# stereo-encoder.net
KiCad netlist of a schematic drawn in EAGLE
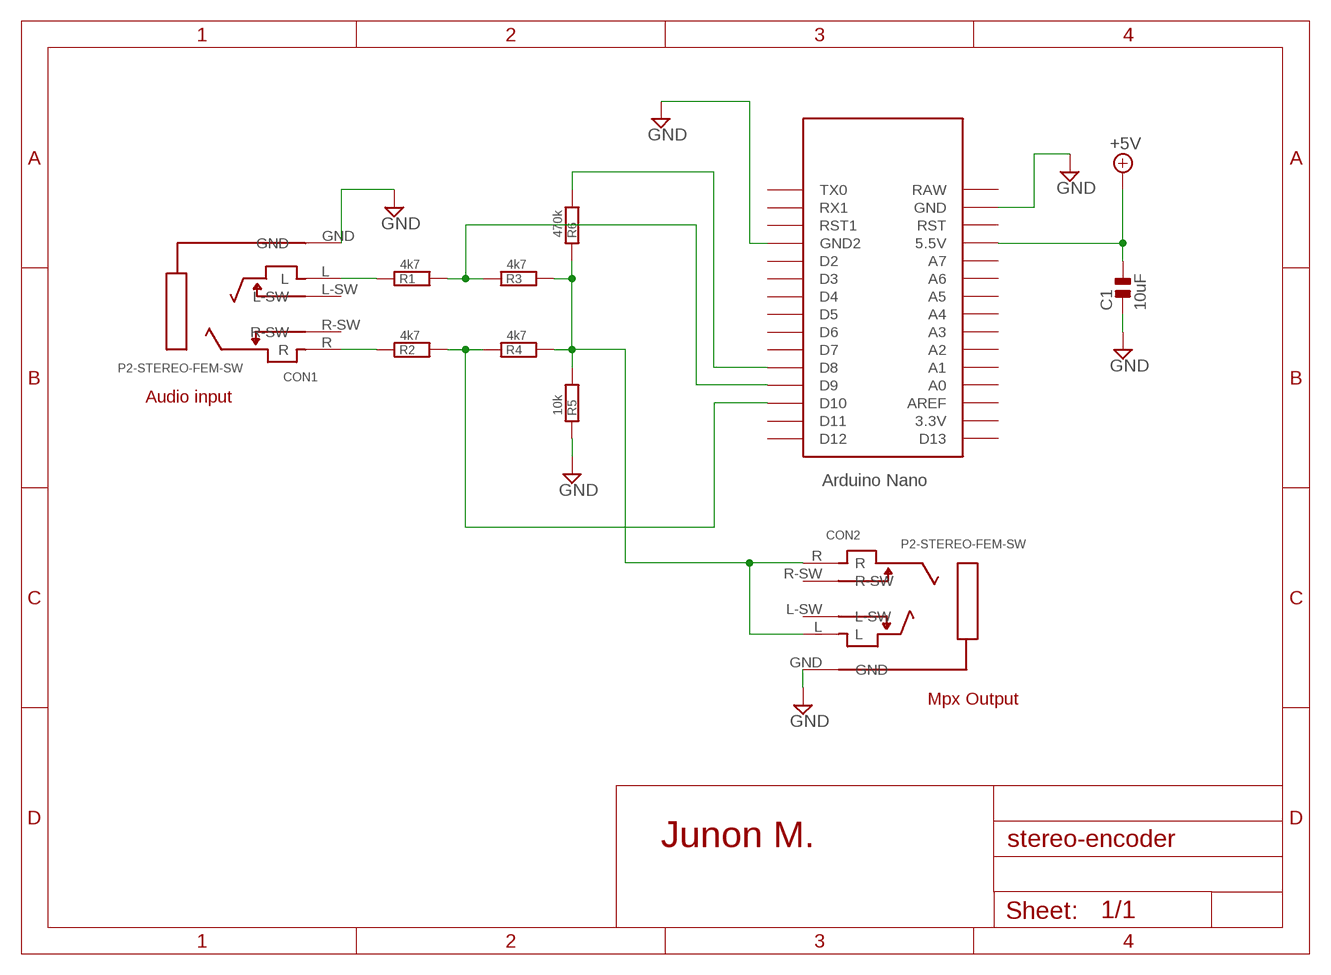
[diagram p0: schematic, sheet 1]

(export (version "E")
  (design (tool "Eeschema 10.0.6"))
  (components
    (comp (ref "C1")
      (value "10uF")
      (footprint "eagle-import:C0805")
      (libsource (lib "eagle-import") (part "C-SMD-0805"))
    )
    (comp (ref "CON1")
      (value "P2-STEREO-FEM-SW")
      (footprint "eagle-import:P2-STEREO-FEM-SW")
      (libsource (lib "eagle-import") (part "P2-STEREO-FEM-SW"))
    )
    (comp (ref "CON2")
      (value "P2-STEREO-FEM-SW")
      (footprint "eagle-import:P2-STEREO-FEM-SW")
      (libsource (lib "eagle-import") (part "P2-STEREO-FEM-SW"))
    )
    (comp (ref "R1")
      (value "4k7")
      (footprint "eagle-import:0207_10")
      (libsource (lib "eagle-import") (part "1/4W"))
    )
    (comp (ref "R2")
      (value "4k7")
      (footprint "eagle-import:0207_10")
      (libsource (lib "eagle-import") (part "1/4W"))
    )
    (comp (ref "R3")
      (value "4k7")
      (footprint "eagle-import:0207_10")
      (libsource (lib "eagle-import") (part "1/4W"))
    )
    (comp (ref "R4")
      (value "4k7")
      (footprint "eagle-import:0207_10")
      (libsource (lib "eagle-import") (part "1/4W"))
    )
    (comp (ref "R5")
      (value "10k")
      (footprint "eagle-import:0207_10")
      (libsource (lib "eagle-import") (part "1/4W"))
    )
    (comp (ref "R6")
      (value "470k")
      (footprint "eagle-import:0207_10")
      (libsource (lib "eagle-import") (part "1/4W"))
    )
    (comp (ref "U$1")
      (value "NANO")
      (footprint "eagle-import:NANO")
      (libsource (lib "eagle-import") (part "NANO"))
    )
  )
  (nets
    (net (code "1") (name "+5V") (class "Default")
      (node (ref "C1") (pin "2") (pinfunction "2_2") (pintype "passive"))
      (node (ref "U$1") (pin "5V") (pinfunction "5.5V_5V") (pintype "bidirectional"))
    )
    (net (code "2") (name "GND") (class "Default")
      (node (ref "C1") (pin "1") (pinfunction "1_1") (pintype "passive"))
      (node (ref "CON1") (pin "GND") (pinfunction "GND_GND") (pintype "passive"))
      (node (ref "CON2") (pin "GND") (pinfunction "GND_GND") (pintype "passive"))
      (node (ref "R5") (pin "1") (pinfunction "1_1") (pintype "passive"))
      (node (ref "U$1") (pin "GND") (pinfunction "GND_GND") (pintype "bidirectional"))
      (node (ref "U$1") (pin "GND1") (pinfunction "GND2_GND1") (pintype "bidirectional"))
    )
    (net (code "3") (name "Net-(CON1-PadL)") (class "Default")
      (node (ref "CON1") (pin "L") (pinfunction "L_L") (pintype "passive"))
      (node (ref "R1") (pin "1") (pinfunction "1_1") (pintype "passive"))
    )
    (net (code "4") (name "Net-(CON1-PadR)") (class "Default")
      (node (ref "CON1") (pin "R") (pinfunction "R_R") (pintype "passive"))
      (node (ref "R2") (pin "1") (pinfunction "1_1") (pintype "passive"))
    )
    (net (code "5") (name "Net-(CON2-PadL)") (class "Default")
      (node (ref "CON2") (pin "L") (pinfunction "L_L") (pintype "passive"))
      (node (ref "CON2") (pin "R") (pinfunction "R_R") (pintype "passive"))
      (node (ref "R3") (pin "2") (pinfunction "2_2") (pintype "passive"))
      (node (ref "R4") (pin "2") (pinfunction "2_2") (pintype "passive"))
      (node (ref "R5") (pin "2") (pinfunction "2_2") (pintype "passive"))
      (node (ref "R6") (pin "1") (pinfunction "1_1") (pintype "passive"))
    )
    (net (code "6") (name "Net-(R1-Pad2)") (class "Default")
      (node (ref "R1") (pin "2") (pinfunction "2_2") (pintype "passive"))
      (node (ref "R3") (pin "1") (pinfunction "1_1") (pintype "passive"))
      (node (ref "U$1") (pin "D9") (pinfunction "D9_D9") (pintype "bidirectional"))
    )
    (net (code "7") (name "Net-(R2-Pad2)") (class "Default")
      (node (ref "R2") (pin "2") (pinfunction "2_2") (pintype "passive"))
      (node (ref "R4") (pin "1") (pinfunction "1_1") (pintype "passive"))
      (node (ref "U$1") (pin "D10") (pinfunction "D10_D10") (pintype "bidirectional"))
    )
    (net (code "8") (name "Net-(R6-Pad2)") (class "Default")
      (node (ref "R6") (pin "2") (pinfunction "2_2") (pintype "passive"))
      (node (ref "U$1") (pin "D8") (pinfunction "D8_D8") (pintype "bidirectional"))
    )
    (net (code "9") (name "unconnected-(CON1-PadL-SW)") (class "Default")
      (node (ref "CON1") (pin "L-SW") (pinfunction "L-SW_L-SW") (pintype "passive"))
    )
    (net (code "10") (name "unconnected-(CON1-PadR-SW)") (class "Default")
      (node (ref "CON1") (pin "R-SW") (pinfunction "R-SW_R-SW") (pintype "passive"))
    )
    (net (code "11") (name "unconnected-(CON2-PadL-SW)") (class "Default")
      (node (ref "CON2") (pin "L-SW") (pinfunction "L-SW_L-SW") (pintype "passive"))
    )
    (net (code "12") (name "unconnected-(CON2-PadR-SW)") (class "Default")
      (node (ref "CON2") (pin "R-SW") (pinfunction "R-SW_R-SW") (pintype "passive"))
    )
    (net (code "13") (name "unconnected-(U$1-Pad3.3V)") (class "Default")
      (node (ref "U$1") (pin "3.3V") (pinfunction "3.3V_3.3V") (pintype "bidirectional"))
    )
    (net (code "14") (name "unconnected-(U$1-PadA0)") (class "Default")
      (node (ref "U$1") (pin "A0") (pinfunction "A0_A0") (pintype "bidirectional"))
    )
    (net (code "15") (name "unconnected-(U$1-PadA1)") (class "Default")
      (node (ref "U$1") (pin "A1") (pinfunction "A1_A1") (pintype "bidirectional"))
    )
    (net (code "16") (name "unconnected-(U$1-PadA2)") (class "Default")
      (node (ref "U$1") (pin "A2") (pinfunction "A2_A2") (pintype "bidirectional"))
    )
    (net (code "17") (name "unconnected-(U$1-PadA3)") (class "Default")
      (node (ref "U$1") (pin "A3") (pinfunction "A3_A3") (pintype "bidirectional"))
    )
    (net (code "18") (name "unconnected-(U$1-PadA4)") (class "Default")
      (node (ref "U$1") (pin "A4") (pinfunction "A4_A4") (pintype "bidirectional"))
    )
    (net (code "19") (name "unconnected-(U$1-PadA5)") (class "Default")
      (node (ref "U$1") (pin "A5") (pinfunction "A5_A5") (pintype "bidirectional"))
    )
    (net (code "20") (name "unconnected-(U$1-PadA6)") (class "Default")
      (node (ref "U$1") (pin "A6") (pinfunction "A6_A6") (pintype "bidirectional"))
    )
    (net (code "21") (name "unconnected-(U$1-PadA7)") (class "Default")
      (node (ref "U$1") (pin "A7") (pinfunction "A7_A7") (pintype "bidirectional"))
    )
    (net (code "22") (name "unconnected-(U$1-PadAREF)") (class "Default")
      (node (ref "U$1") (pin "AREF") (pinfunction "AREF_AREF") (pintype "bidirectional"))
    )
    (net (code "23") (name "unconnected-(U$1-PadD2)") (class "Default")
      (node (ref "U$1") (pin "D2") (pinfunction "D2_D2") (pintype "bidirectional"))
    )
    (net (code "24") (name "unconnected-(U$1-PadD3)") (class "Default")
      (node (ref "U$1") (pin "D3") (pinfunction "D3_D3") (pintype "bidirectional"))
    )
    (net (code "25") (name "unconnected-(U$1-PadD4)") (class "Default")
      (node (ref "U$1") (pin "D4") (pinfunction "D4_D4") (pintype "bidirectional"))
    )
    (net (code "26") (name "unconnected-(U$1-PadD5)") (class "Default")
      (node (ref "U$1") (pin "D5") (pinfunction "D5_D5") (pintype "bidirectional"))
    )
    (net (code "27") (name "unconnected-(U$1-PadD6)") (class "Default")
      (node (ref "U$1") (pin "D6") (pinfunction "D6_D6") (pintype "bidirectional"))
    )
    (net (code "28") (name "unconnected-(U$1-PadD7)") (class "Default")
      (node (ref "U$1") (pin "D7") (pinfunction "D7_D7") (pintype "bidirectional"))
    )
    (net (code "29") (name "unconnected-(U$1-PadD11)") (class "Default")
      (node (ref "U$1") (pin "D11") (pinfunction "D11_D11") (pintype "bidirectional"))
    )
    (net (code "30") (name "unconnected-(U$1-PadD12)") (class "Default")
      (node (ref "U$1") (pin "D12") (pinfunction "D12_D12") (pintype "bidirectional"))
    )
    (net (code "31") (name "unconnected-(U$1-PadD13)") (class "Default")
      (node (ref "U$1") (pin "D13") (pinfunction "D13_D13") (pintype "bidirectional"))
    )
    (net (code "32") (name "unconnected-(U$1-PadICSP1)") (class "Default")
      (node (ref "U$1") (pin "ICSP1") (pinfunction "ICSP1_ICSP1") (pintype "bidirectional"))
    )
    (net (code "33") (name "unconnected-(U$1-PadICSP2)") (class "Default")
      (node (ref "U$1") (pin "ICSP2") (pinfunction "ICSP2_ICSP2") (pintype "bidirectional"))
    )
    (net (code "34") (name "unconnected-(U$1-PadICSP3)") (class "Default")
      (node (ref "U$1") (pin "ICSP3") (pinfunction "ICSP3_ICSP3") (pintype "bidirectional"))
    )
    (net (code "35") (name "unconnected-(U$1-PadICSP4)") (class "Default")
      (node (ref "U$1") (pin "ICSP4") (pinfunction "ICSP4_ICSP4") (pintype "bidirectional"))
    )
    (net (code "36") (name "unconnected-(U$1-PadICSP5)") (class "Default")
      (node (ref "U$1") (pin "ICSP5") (pinfunction "ICSP5_ICSP5") (pintype "bidirectional"))
    )
    (net (code "37") (name "unconnected-(U$1-PadICSP6)") (class "Default")
      (node (ref "U$1") (pin "ICSP6") (pinfunction "ICSP6_ICSP6") (pintype "bidirectional"))
    )
    (net (code "38") (name "unconnected-(U$1-PadRAW)") (class "Default")
      (node (ref "U$1") (pin "RAW") (pinfunction "RAW_RAW") (pintype "bidirectional"))
    )
    (net (code "39") (name "unconnected-(U$1-PadRST)") (class "Default")
      (node (ref "U$1") (pin "RST") (pinfunction "RST_RST") (pintype "bidirectional"))
    )
    (net (code "40") (name "unconnected-(U$1-PadRST1)") (class "Default")
      (node (ref "U$1") (pin "RST1") (pinfunction "RST1_RST1") (pintype "bidirectional"))
    )
    (net (code "41") (name "unconnected-(U$1-PadRX1)") (class "Default")
      (node (ref "U$1") (pin "RX1") (pinfunction "RX1_RX1") (pintype "bidirectional"))
    )
    (net (code "42") (name "unconnected-(U$1-PadTX0)") (class "Default")
      (node (ref "U$1") (pin "TX0") (pinfunction "TX0_TX0") (pintype "bidirectional"))
    )
  )
)
